# ADXL335.net
KiCad netlist of a schematic drawn in EAGLE
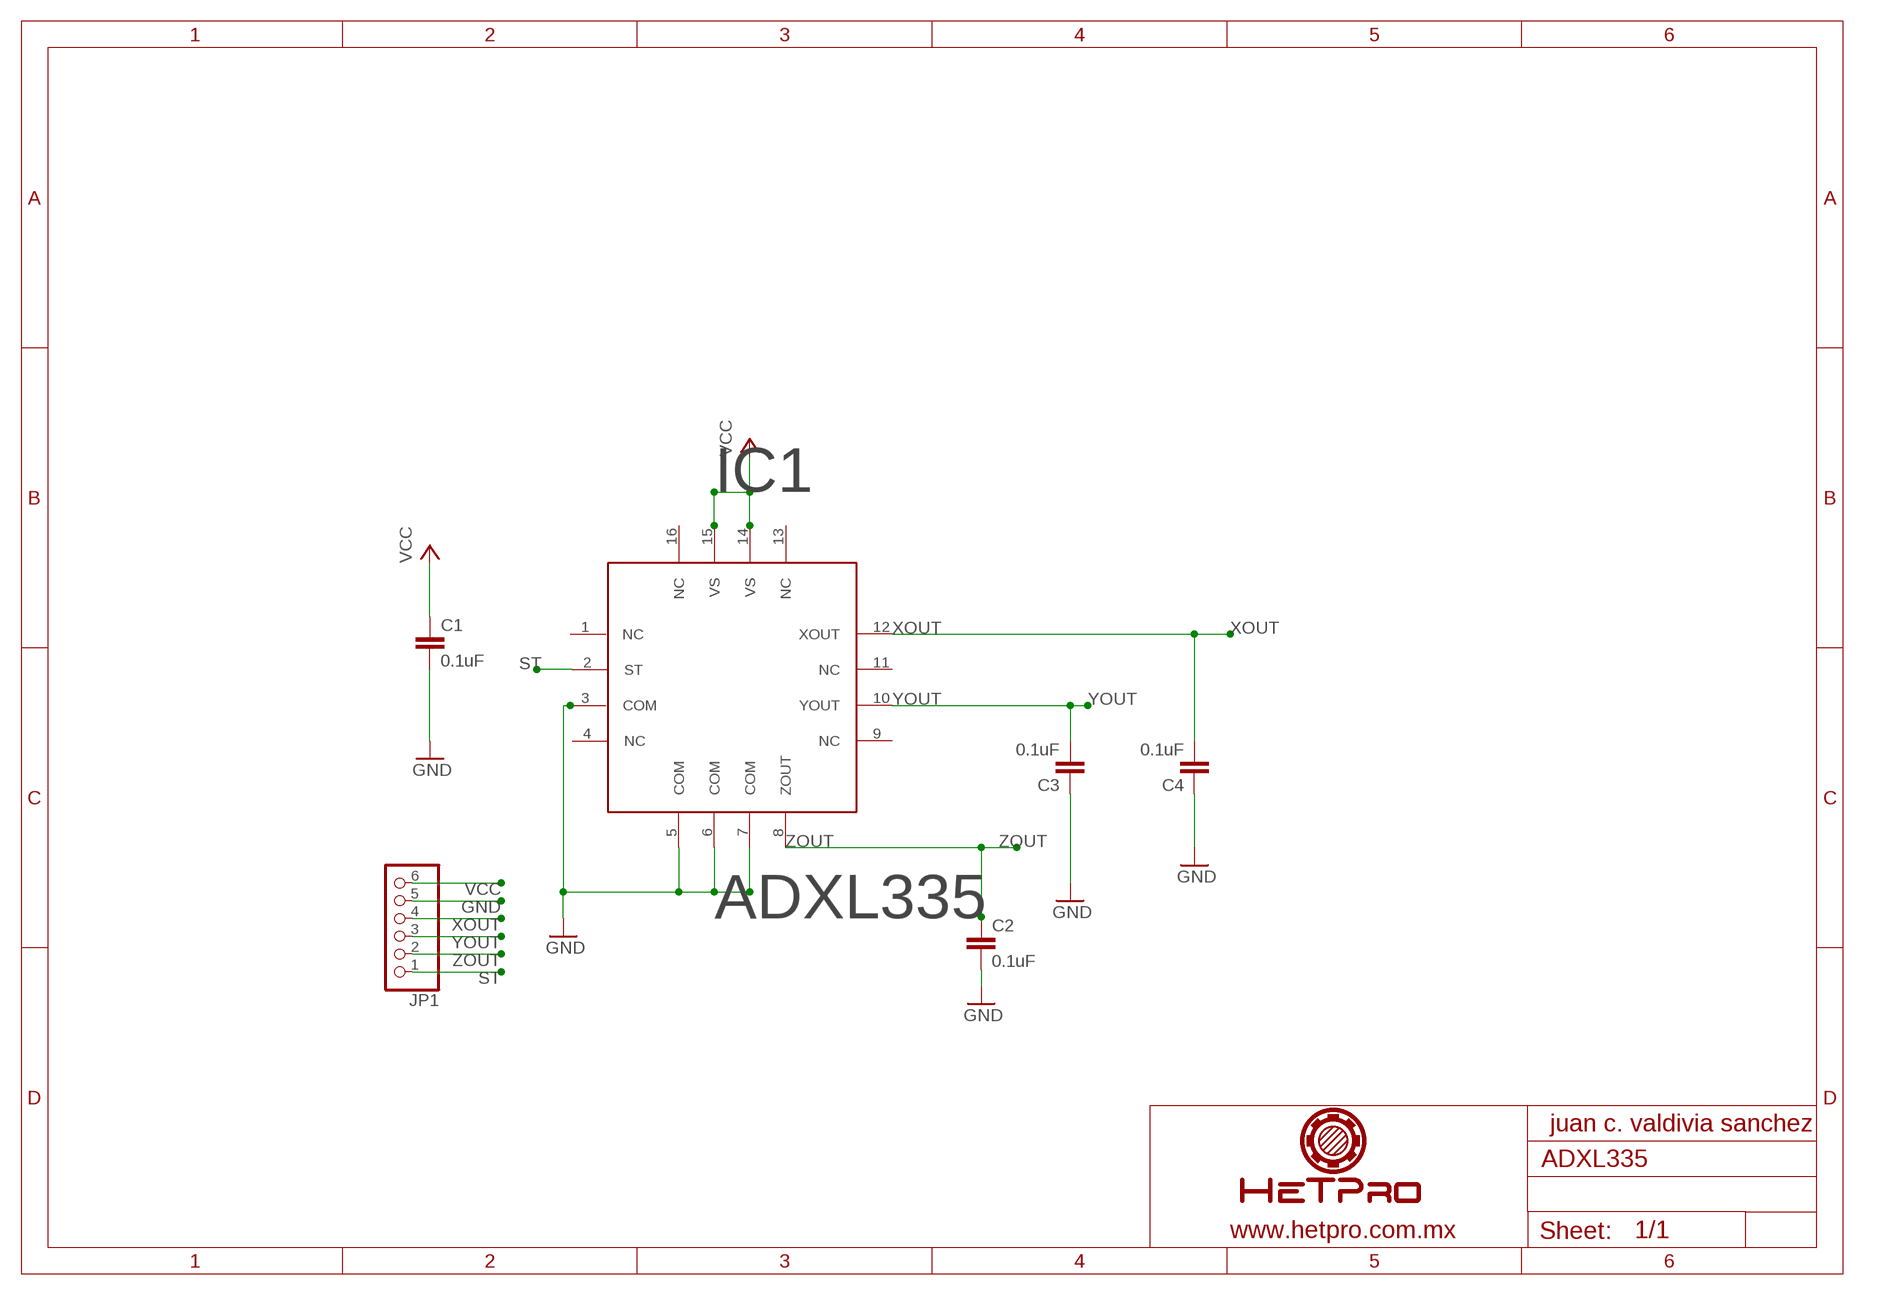
[diagram p0: schematic, sheet 1]

(export (version "E")
  (design (tool "Eeschema 10.0.6"))
  (components
    (comp (ref "C1")
      (value "0.1uF")
      (footprint "eagle-import:C0603")
      (libsource (lib "eagle-import") (part "C-EUC0603"))
    )
    (comp (ref "C2")
      (value "0.1uF")
      (footprint "eagle-import:C0603")
      (libsource (lib "eagle-import") (part "C-EUC0603"))
    )
    (comp (ref "C3")
      (value "0.1uF")
      (footprint "eagle-import:C0603")
      (libsource (lib "eagle-import") (part "C-EUC0603"))
    )
    (comp (ref "C4")
      (value "0.1uF")
      (footprint "eagle-import:C0603")
      (libsource (lib "eagle-import") (part "C-EUC0603"))
    )
    (comp (ref "IC1")
      (value "ADXL335")
      (footprint "eagle-import:ADXL335")
      (libsource (lib "eagle-import") (part "ADXL335"))
    )
    (comp (ref "JP1")
      (value "PINHD-1X6")
      (footprint "eagle-import:1X06")
      (libsource (lib "eagle-import") (part "PINHD-1X6"))
    )
  )
  (nets
    (net (code "1") (name "/ST") (class "Default")
      (node (ref "IC1") (pin "2") (pinfunction "ST_2") (pintype "bidirectional"))
      (node (ref "JP1") (pin "1") (pinfunction "1_1") (pintype "passive"))
    )
    (net (code "2") (name "/XOUT") (class "Default")
      (node (ref "C4") (pin "2") (pinfunction "2_2") (pintype "passive"))
      (node (ref "IC1") (pin "12") (pinfunction "XOUT_12") (pintype "bidirectional"))
      (node (ref "JP1") (pin "4") (pinfunction "4_4") (pintype "passive"))
    )
    (net (code "3") (name "/YOUT") (class "Default")
      (node (ref "C3") (pin "2") (pinfunction "2_2") (pintype "passive"))
      (node (ref "IC1") (pin "10") (pinfunction "YOUT_10") (pintype "bidirectional"))
      (node (ref "JP1") (pin "3") (pinfunction "3_3") (pintype "passive"))
    )
    (net (code "4") (name "/ZOUT") (class "Default")
      (node (ref "C2") (pin "1") (pinfunction "1_1") (pintype "passive"))
      (node (ref "IC1") (pin "8") (pinfunction "ZOUT_8") (pintype "bidirectional"))
      (node (ref "JP1") (pin "2") (pinfunction "2_2") (pintype "passive"))
    )
    (net (code "5") (name "GND") (class "Default")
      (node (ref "C1") (pin "2") (pinfunction "2_2") (pintype "passive"))
      (node (ref "C2") (pin "2") (pinfunction "2_2") (pintype "passive"))
      (node (ref "C3") (pin "1") (pinfunction "1_1") (pintype "passive"))
      (node (ref "C4") (pin "1") (pinfunction "1_1") (pintype "passive"))
      (node (ref "IC1") (pin "3") (pinfunction "COM_3") (pintype "bidirectional"))
      (node (ref "IC1") (pin "5") (pinfunction "COM_5") (pintype "bidirectional"))
      (node (ref "IC1") (pin "6") (pinfunction "COM_6") (pintype "bidirectional"))
      (node (ref "IC1") (pin "7") (pinfunction "COM_7") (pintype "bidirectional"))
      (node (ref "JP1") (pin "5") (pinfunction "5_5") (pintype "passive"))
    )
    (net (code "6") (name "VCC") (class "Default")
      (node (ref "C1") (pin "1") (pinfunction "1_1") (pintype "passive"))
      (node (ref "IC1") (pin "14") (pinfunction "VS_14") (pintype "bidirectional"))
      (node (ref "IC1") (pin "15") (pinfunction "VS_15") (pintype "bidirectional"))
      (node (ref "JP1") (pin "6") (pinfunction "6_6") (pintype "passive"))
    )
    (net (code "7") (name "unconnected-(IC1-NC-Pad1)") (class "Default")
      (node (ref "IC1") (pin "1") (pinfunction "NC_1") (pintype "bidirectional"))
    )
    (net (code "8") (name "unconnected-(IC1-NC-Pad4)") (class "Default")
      (node (ref "IC1") (pin "4") (pinfunction "NC_4") (pintype "bidirectional"))
    )
    (net (code "9") (name "unconnected-(IC1-NC-Pad9)") (class "Default")
      (node (ref "IC1") (pin "9") (pinfunction "NC_9") (pintype "bidirectional"))
    )
    (net (code "10") (name "unconnected-(IC1-NC-Pad11)") (class "Default")
      (node (ref "IC1") (pin "11") (pinfunction "NC_11") (pintype "bidirectional"))
    )
    (net (code "11") (name "unconnected-(IC1-NC-Pad13)") (class "Default")
      (node (ref "IC1") (pin "13") (pinfunction "NC_13") (pintype "bidirectional"))
    )
    (net (code "12") (name "unconnected-(IC1-NC-Pad16)") (class "Default")
      (node (ref "IC1") (pin "16") (pinfunction "NC_16") (pintype "bidirectional"))
    )
  )
)
